# Level_Shifter.net
KiCad netlist of a schematic drawn in Altium Designer
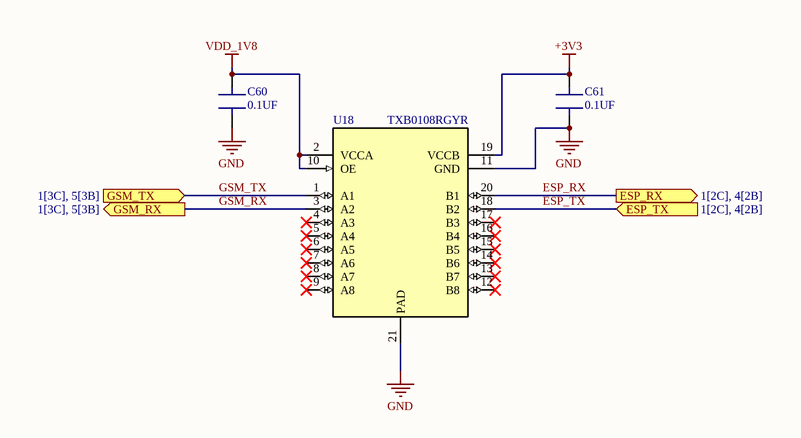
[diagram p0: Level Shifter.SchDoc]

(export (version "E")
  (design (tool "Eeschema 10.0.6"))
  (components
    (comp (ref "C60")
      (value "0.1UF")
      (footprint "CAP: 0603")
      (description "CAP SMD 0603")
      (libsource (lib "HZSchLib") (part "CAP 0603"))
    )
    (comp (ref "C61")
      (value "0.1UF")
      (footprint "CAP: 0603")
      (description "CAP SMD 0603")
      (libsource (lib "HZSchLib") (part "CAP 0603"))
    )
    (comp (ref "U18")
      (value "TXB0108RGYR")
      (footprint "20-VQFN (3.5x4.5)")
      (description "IC 8-BIT TRNSLTR 15KV ESD 20VQFN")
      (fields (field (name "MANUFACTURER") "Texas Instruments"))
      (libsource (lib "HZSchLib") (part "TXB0108RGYR"))
    )
  )
  (nets
    (net (code "1") (name "+3V3") (class "Default")
      (node (ref "C61") (pin "1") (pinfunction "A_1") (pintype "passive"))
      (node (ref "U18") (pin "19") (pinfunction "VCCB_19") (pintype "power_in"))
    )
    (net (code "2") (name "/ESP_RX") (class "Default")
      (node (ref "U18") (pin "20") (pinfunction "B1_20") (pintype "bidirectional"))
    )
    (net (code "3") (name "/ESP_TX") (class "Default")
      (node (ref "U18") (pin "18") (pinfunction "B2_18") (pintype "bidirectional"))
    )
    (net (code "4") (name "/GSM_RX") (class "Default")
      (node (ref "U18") (pin "3") (pinfunction "A2_3") (pintype "bidirectional"))
    )
    (net (code "5") (name "/GSM_TX") (class "Default")
      (node (ref "U18") (pin "1") (pinfunction "A1_1") (pintype "bidirectional"))
    )
    (net (code "6") (name "GND") (class "Default")
      (node (ref "C60") (pin "2") (pinfunction "B_2") (pintype "passive"))
      (node (ref "C61") (pin "2") (pinfunction "B_2") (pintype "passive"))
      (node (ref "U18") (pin "11") (pinfunction "GND_11") (pintype "power_in"))
      (node (ref "U18") (pin "21") (pinfunction "PAD_21") (pintype "power_in"))
    )
    (net (code "7") (name "VDD_1V8") (class "Default")
      (node (ref "C60") (pin "1") (pinfunction "A_1") (pintype "passive"))
      (node (ref "U18") (pin "10") (pinfunction "OE_10") (pintype "input"))
      (node (ref "U18") (pin "2") (pinfunction "VCCA_2") (pintype "power_in"))
    )
    (net (code "8") (name "unconnected-(U18-A3-Pad4)") (class "Default")
      (node (ref "U18") (pin "4") (pinfunction "A3_4") (pintype "bidirectional+no_connect"))
    )
    (net (code "9") (name "unconnected-(U18-A4-Pad5)") (class "Default")
      (node (ref "U18") (pin "5") (pinfunction "A4_5") (pintype "bidirectional+no_connect"))
    )
    (net (code "10") (name "unconnected-(U18-A5-Pad6)") (class "Default")
      (node (ref "U18") (pin "6") (pinfunction "A5_6") (pintype "bidirectional+no_connect"))
    )
    (net (code "11") (name "unconnected-(U18-A6-Pad7)") (class "Default")
      (node (ref "U18") (pin "7") (pinfunction "A6_7") (pintype "bidirectional+no_connect"))
    )
    (net (code "12") (name "unconnected-(U18-A7-Pad8)") (class "Default")
      (node (ref "U18") (pin "8") (pinfunction "A7_8") (pintype "bidirectional+no_connect"))
    )
    (net (code "13") (name "unconnected-(U18-A8-Pad9)") (class "Default")
      (node (ref "U18") (pin "9") (pinfunction "A8_9") (pintype "bidirectional+no_connect"))
    )
    (net (code "14") (name "unconnected-(U18-B3-Pad17)") (class "Default")
      (node (ref "U18") (pin "17") (pinfunction "B3_17") (pintype "bidirectional+no_connect"))
    )
    (net (code "15") (name "unconnected-(U18-B4-Pad16)") (class "Default")
      (node (ref "U18") (pin "16") (pinfunction "B4_16") (pintype "bidirectional+no_connect"))
    )
    (net (code "16") (name "unconnected-(U18-B5-Pad15)") (class "Default")
      (node (ref "U18") (pin "15") (pinfunction "B5_15") (pintype "bidirectional+no_connect"))
    )
    (net (code "17") (name "unconnected-(U18-B6-Pad14)") (class "Default")
      (node (ref "U18") (pin "14") (pinfunction "B6_14") (pintype "bidirectional+no_connect"))
    )
    (net (code "18") (name "unconnected-(U18-B7-Pad13)") (class "Default")
      (node (ref "U18") (pin "13") (pinfunction "B7_13") (pintype "bidirectional+no_connect"))
    )
    (net (code "19") (name "unconnected-(U18-B8-Pad12)") (class "Default")
      (node (ref "U18") (pin "12") (pinfunction "B8_12") (pintype "bidirectional+no_connect"))
    )
  )
)
